# stm32.net
KiCad netlist of a schematic drawn in EAGLE
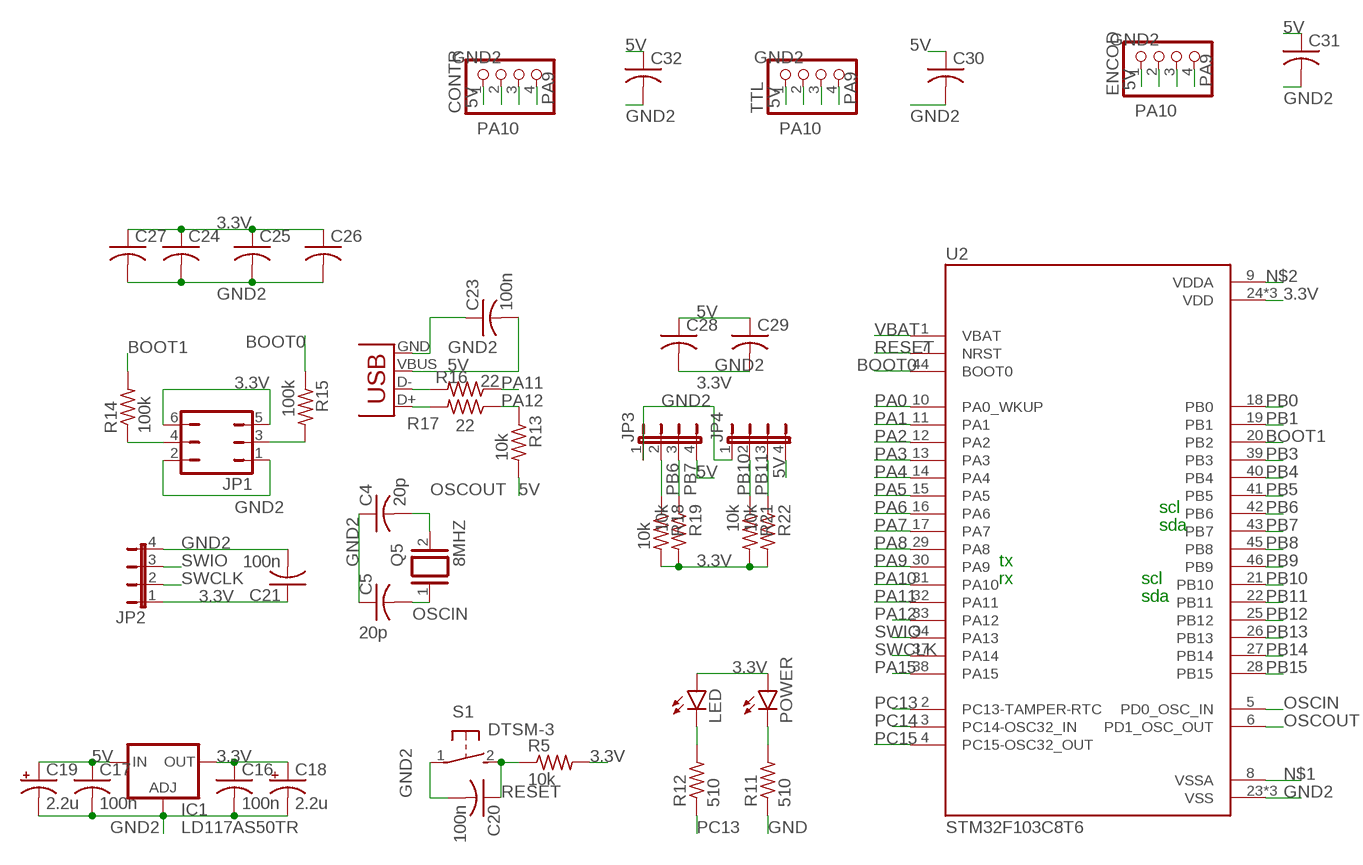
[diagram p0: schematic, sheet 1]

(export (version "E")
  (design (tool "Eeschema 10.0.6"))
  (components
    (comp (ref "C4")
      (value "20p")
      (footprint "eagle-import:C1206")
      (libsource (lib "eagle-import") (part "C-USC1206"))
    )
    (comp (ref "C5")
      (value "20p")
      (footprint "eagle-import:C1206")
      (libsource (lib "eagle-import") (part "C-USC1206"))
    )
    (comp (ref "C16")
      (value "100n")
      (footprint "eagle-import:C1206")
      (libsource (lib "eagle-import") (part "C-USC1206"))
    )
    (comp (ref "C17")
      (value "100n")
      (footprint "eagle-import:C1206")
      (libsource (lib "eagle-import") (part "C-USC1206"))
    )
    (comp (ref "C18")
      (value "2.2u")
      (footprint "eagle-import:E2-5")
      (libsource (lib "eagle-import") (part "CPOL-USE2-5"))
    )
    (comp (ref "C19")
      (value "2.2u")
      (footprint "eagle-import:E2-5")
      (libsource (lib "eagle-import") (part "CPOL-USE2-5"))
    )
    (comp (ref "C20")
      (value "100n")
      (footprint "eagle-import:C1206")
      (libsource (lib "eagle-import") (part "C-USC1206"))
    )
    (comp (ref "C21")
      (value "100n")
      (footprint "eagle-import:C1206")
      (libsource (lib "eagle-import") (part "C-USC1206"))
    )
    (comp (ref "C23")
      (value "100n")
      (footprint "eagle-import:C1206")
      (libsource (lib "eagle-import") (part "C-USC1206"))
    )
    (comp (ref "C24")
      (value "C-USC1206")
      (footprint "eagle-import:C1206")
      (libsource (lib "eagle-import") (part "C-USC1206"))
    )
    (comp (ref "C25")
      (value "C-USC1206")
      (footprint "eagle-import:C1206")
      (libsource (lib "eagle-import") (part "C-USC1206"))
    )
    (comp (ref "C26")
      (value "C-USC1206")
      (footprint "eagle-import:C1206")
      (libsource (lib "eagle-import") (part "C-USC1206"))
    )
    (comp (ref "C27")
      (value "C-USC1206")
      (footprint "eagle-import:C1206")
      (libsource (lib "eagle-import") (part "C-USC1206"))
    )
    (comp (ref "C28")
      (value "C-USC1206")
      (footprint "eagle-import:C1206")
      (libsource (lib "eagle-import") (part "C-USC1206"))
    )
    (comp (ref "C29")
      (value "C-USC1206")
      (footprint "eagle-import:C1206")
      (libsource (lib "eagle-import") (part "C-USC1206"))
    )
    (comp (ref "C30")
      (value "C-USC1206")
      (footprint "eagle-import:C1206")
      (libsource (lib "eagle-import") (part "C-USC1206"))
    )
    (comp (ref "C31")
      (value "C-USC1206")
      (footprint "eagle-import:C1206")
      (libsource (lib "eagle-import") (part "C-USC1206"))
    )
    (comp (ref "C32")
      (value "C-USC1206")
      (footprint "eagle-import:C1206")
      (libsource (lib "eagle-import") (part "C-USC1206"))
    )
    (comp (ref "CONTR")
      (value "PINHD-1X4")
      (footprint "eagle-import:1X04")
      (libsource (lib "eagle-import") (part "PINHD-1X4"))
    )
    (comp (ref "ENCOD")
      (value "PINHD-1X4")
      (footprint "eagle-import:1X04")
      (libsource (lib "eagle-import") (part "PINHD-1X4"))
    )
    (comp (ref "IC1")
      (value "LD117AS50TR")
      (footprint "eagle-import:SOT223")
      (libsource (lib "eagle-import") (part "LD117A?S50TR"))
    )
    (comp (ref "JP1")
      (value "JP3Q")
      (footprint "eagle-import:JP3Q")
      (libsource (lib "eagle-import") (part "JP3Q"))
    )
    (comp (ref "JP2")
      (value "JP4E")
      (footprint "eagle-import:JP4")
      (libsource (lib "eagle-import") (part "JP4E"))
    )
    (comp (ref "JP3")
      (value "JP4E")
      (footprint "eagle-import:JP4")
      (libsource (lib "eagle-import") (part "JP4E"))
    )
    (comp (ref "JP4")
      (value "JP4E")
      (footprint "eagle-import:JP4")
      (libsource (lib "eagle-import") (part "JP4E"))
    )
    (comp (ref "LED")
      (value "LEDCHIPLED_1206")
      (footprint "eagle-import:CHIPLED_1206")
      (libsource (lib "eagle-import") (part "LEDCHIPLED_1206"))
    )
    (comp (ref "POWER")
      (value "LEDCHIPLED_1206")
      (footprint "eagle-import:CHIPLED_1206")
      (libsource (lib "eagle-import") (part "LEDCHIPLED_1206"))
    )
    (comp (ref "Q5")
      (value "8MHZ")
      (footprint "eagle-import:QS")
      (libsource (lib "eagle-import") (part "XTAL/S"))
    )
    (comp (ref "R5")
      (value "10k")
      (footprint "eagle-import:R1206")
      (libsource (lib "eagle-import") (part "R-US_R1206"))
    )
    (comp (ref "R11")
      (value "510")
      (footprint "eagle-import:R1206")
      (libsource (lib "eagle-import") (part "R-US_R1206"))
    )
    (comp (ref "R12")
      (value "510")
      (footprint "eagle-import:R1206")
      (libsource (lib "eagle-import") (part "R-US_R1206"))
    )
    (comp (ref "R13")
      (value "10k")
      (footprint "eagle-import:R1206")
      (libsource (lib "eagle-import") (part "R-US_R1206"))
    )
    (comp (ref "R14")
      (value "100k")
      (footprint "eagle-import:R1206")
      (libsource (lib "eagle-import") (part "R-US_R1206"))
    )
    (comp (ref "R15")
      (value "100k")
      (footprint "eagle-import:R1206")
      (libsource (lib "eagle-import") (part "R-US_R1206"))
    )
    (comp (ref "R16")
      (value "22")
      (footprint "eagle-import:R1206")
      (libsource (lib "eagle-import") (part "R-US_R1206"))
    )
    (comp (ref "R17")
      (value "22")
      (footprint "eagle-import:R1206")
      (libsource (lib "eagle-import") (part "R-US_R1206"))
    )
    (comp (ref "R18")
      (value "10k")
      (footprint "eagle-import:R1206")
      (libsource (lib "eagle-import") (part "R-US_R1206"))
    )
    (comp (ref "R19")
      (value "10k")
      (footprint "eagle-import:R1206")
      (libsource (lib "eagle-import") (part "R-US_R1206"))
    )
    (comp (ref "R21")
      (value "10k")
      (footprint "eagle-import:R1206")
      (libsource (lib "eagle-import") (part "R-US_R1206"))
    )
    (comp (ref "R22")
      (value "10k")
      (footprint "eagle-import:R1206")
      (libsource (lib "eagle-import") (part "R-US_R1206"))
    )
    (comp (ref "S1")
      (value "DTSM-3")
      (footprint "eagle-import:DTSM-3")
      (libsource (lib "eagle-import") (part "DTSM-3"))
    )
    (comp (ref "TTL")
      (value "PINHD-1X4")
      (footprint "eagle-import:1X04")
      (libsource (lib "eagle-import") (part "PINHD-1X4"))
    )
    (comp (ref "U2")
      (value "STM32F103C8T6")
      (footprint "eagle-import:QFP50P900X900X160-48N")
      (fields (field (name "MF") "STMicroelectronics"))
      (libsource (lib "eagle-import") (part "STM32F103C8T6"))
    )
    (comp (ref "X1")
      (value "USB-MB-S")
      (footprint "eagle-import:USB-MB-S")
      (libsource (lib "eagle-import") (part "USB-MB-S"))
    )
  )
  (nets
    (net (code "1") (name "/3.3V") (class "Default")
      (node (ref "C16") (pin "1") (pinfunction "1_1") (pintype "passive"))
      (node (ref "C18") (pin "+") (pinfunction "+_+") (pintype "passive"))
      (node (ref "C21") (pin "1") (pinfunction "1_1") (pintype "passive"))
      (node (ref "C24") (pin "1") (pinfunction "1_1") (pintype "passive"))
      (node (ref "C25") (pin "1") (pinfunction "1_1") (pintype "passive"))
      (node (ref "C26") (pin "1") (pinfunction "1_1") (pintype "passive"))
      (node (ref "C27") (pin "1") (pinfunction "1_1") (pintype "passive"))
      (node (ref "IC1") (pin "4") (pinfunction "OUT_4") (pintype "passive"))
      (node (ref "JP1") (pin "5") (pinfunction "5_5") (pintype "passive"))
      (node (ref "JP1") (pin "6") (pinfunction "6_6") (pintype "passive"))
      (node (ref "JP2") (pin "1") (pinfunction "1_1") (pintype "passive"))
      (node (ref "LED") (pin "A") (pinfunction "A_A") (pintype "passive"))
      (node (ref "POWER") (pin "A") (pinfunction "A_A") (pintype "passive"))
      (node (ref "R18") (pin "2") (pinfunction "2_2") (pintype "passive"))
      (node (ref "R19") (pin "2") (pinfunction "2_2") (pintype "passive"))
      (node (ref "R21") (pin "2") (pinfunction "2_2") (pintype "passive"))
      (node (ref "R22") (pin "2") (pinfunction "2_2") (pintype "passive"))
      (node (ref "R5") (pin "2") (pinfunction "2_2") (pintype "passive"))
      (node (ref "U2") (pin "24") (pinfunction "VDD_24") (pintype "power_in"))
      (node (ref "U2") (pin "36") (pinfunction "VDD_36") (pintype "power_in"))
      (node (ref "U2") (pin "48") (pinfunction "VDD_48") (pintype "power_in"))
    )
    (net (code "2") (name "/5V") (class "Default")
      (node (ref "C17") (pin "1") (pinfunction "1_1") (pintype "passive"))
      (node (ref "C19") (pin "+") (pinfunction "+_+") (pintype "passive"))
      (node (ref "C23") (pin "2") (pinfunction "2_2") (pintype "passive"))
      (node (ref "C28") (pin "1") (pinfunction "1_1") (pintype "passive"))
      (node (ref "C29") (pin "1") (pinfunction "1_1") (pintype "passive"))
      (node (ref "C30") (pin "1") (pinfunction "1_1") (pintype "passive"))
      (node (ref "C31") (pin "1") (pinfunction "1_1") (pintype "passive"))
      (node (ref "C32") (pin "1") (pinfunction "1_1") (pintype "passive"))
      (node (ref "CONTR") (pin "1") (pinfunction "1_1") (pintype "passive"))
      (node (ref "ENCOD") (pin "1") (pinfunction "1_1") (pintype "passive"))
      (node (ref "IC1") (pin "3") (pinfunction "IN_3") (pintype "input"))
      (node (ref "JP3") (pin "4") (pinfunction "4_4") (pintype "passive"))
      (node (ref "JP4") (pin "4") (pinfunction "4_4") (pintype "passive"))
      (node (ref "R13") (pin "2") (pinfunction "2_2") (pintype "passive"))
      (node (ref "TTL") (pin "1") (pinfunction "1_1") (pintype "passive"))
      (node (ref "X1") (pin "VBUS") (pinfunction "VBUS_VBUS") (pintype "bidirectional"))
    )
    (net (code "3") (name "/BOOT0") (class "Default")
      (node (ref "R15") (pin "1") (pinfunction "1_1") (pintype "passive"))
      (node (ref "U2") (pin "44") (pinfunction "BOOT0_44") (pintype "input"))
    )
    (net (code "4") (name "/BOOT1") (class "Default")
      (node (ref "R14") (pin "2") (pinfunction "2_2") (pintype "passive"))
      (node (ref "U2") (pin "20") (pinfunction "PB2_20") (pintype "bidirectional"))
    )
    (net (code "5") (name "/GND") (class "Default")
      (node (ref "R11") (pin "1") (pinfunction "1_1") (pintype "passive"))
    )
    (net (code "6") (name "/GND2") (class "Default")
      (node (ref "C16") (pin "2") (pinfunction "2_2") (pintype "passive"))
      (node (ref "C17") (pin "2") (pinfunction "2_2") (pintype "passive"))
      (node (ref "C18") (pin "-") (pinfunction "-_-") (pintype "passive"))
      (node (ref "C19") (pin "-") (pinfunction "-_-") (pintype "passive"))
      (node (ref "C20") (pin "2") (pinfunction "2_2") (pintype "passive"))
      (node (ref "C21") (pin "2") (pinfunction "2_2") (pintype "passive"))
      (node (ref "C23") (pin "1") (pinfunction "1_1") (pintype "passive"))
      (node (ref "C24") (pin "2") (pinfunction "2_2") (pintype "passive"))
      (node (ref "C25") (pin "2") (pinfunction "2_2") (pintype "passive"))
      (node (ref "C26") (pin "2") (pinfunction "2_2") (pintype "passive"))
      (node (ref "C27") (pin "2") (pinfunction "2_2") (pintype "passive"))
      (node (ref "C28") (pin "2") (pinfunction "2_2") (pintype "passive"))
      (node (ref "C29") (pin "2") (pinfunction "2_2") (pintype "passive"))
      (node (ref "C30") (pin "2") (pinfunction "2_2") (pintype "passive"))
      (node (ref "C31") (pin "2") (pinfunction "2_2") (pintype "passive"))
      (node (ref "C32") (pin "2") (pinfunction "2_2") (pintype "passive"))
      (node (ref "C4") (pin "1") (pinfunction "1_1") (pintype "passive"))
      (node (ref "C5") (pin "1") (pinfunction "1_1") (pintype "passive"))
      (node (ref "CONTR") (pin "2") (pinfunction "2_2") (pintype "passive"))
      (node (ref "ENCOD") (pin "2") (pinfunction "2_2") (pintype "passive"))
      (node (ref "IC1") (pin "1") (pinfunction "ADJ_1") (pintype "input"))
      (node (ref "JP1") (pin "1") (pinfunction "1_1") (pintype "passive"))
      (node (ref "JP1") (pin "2") (pinfunction "2_2") (pintype "passive"))
      (node (ref "JP2") (pin "4") (pinfunction "4_4") (pintype "passive"))
      (node (ref "JP3") (pin "1") (pinfunction "1_1") (pintype "passive"))
      (node (ref "JP4") (pin "1") (pinfunction "1_1") (pintype "passive"))
      (node (ref "S1") (pin "1") (pinfunction "1_1") (pintype "passive"))
      (node (ref "TTL") (pin "2") (pinfunction "2_2") (pintype "passive"))
      (node (ref "U2") (pin "23") (pinfunction "VSS_23") (pintype "power_in"))
      (node (ref "U2") (pin "35") (pinfunction "VSS_35") (pintype "power_in"))
      (node (ref "U2") (pin "47") (pinfunction "VSS_47") (pintype "power_in"))
      (node (ref "X1") (pin "GND") (pinfunction "GND_GND") (pintype "bidirectional"))
    )
    (net (code "7") (name "/N$1") (class "Default")
      (node (ref "U2") (pin "8") (pinfunction "VSSA_8") (pintype "power_in"))
    )
    (net (code "8") (name "/N$2") (class "Default")
      (node (ref "U2") (pin "9") (pinfunction "VDDA_9") (pintype "power_in"))
    )
    (net (code "9") (name "/OSCIN") (class "Default")
      (node (ref "C5") (pin "2") (pinfunction "2_2") (pintype "passive"))
      (node (ref "Q5") (pin "1") (pinfunction "1_1") (pintype "passive"))
      (node (ref "U2") (pin "5") (pinfunction "PD0_OSC_IN_5") (pintype "bidirectional"))
    )
    (net (code "10") (name "/OSCOUT") (class "Default")
      (node (ref "C4") (pin "2") (pinfunction "2_2") (pintype "passive"))
      (node (ref "Q5") (pin "2") (pinfunction "2_2") (pintype "passive"))
      (node (ref "U2") (pin "6") (pinfunction "PD1_OSC_OUT_6") (pintype "bidirectional"))
    )
    (net (code "11") (name "/PA0") (class "Default")
      (node (ref "U2") (pin "10") (pinfunction "PA0_WKUP_10") (pintype "bidirectional"))
    )
    (net (code "12") (name "/PA1") (class "Default")
      (node (ref "U2") (pin "11") (pinfunction "PA1_11") (pintype "bidirectional"))
    )
    (net (code "13") (name "/PA2") (class "Default")
      (node (ref "U2") (pin "12") (pinfunction "PA2_12") (pintype "bidirectional"))
    )
    (net (code "14") (name "/PA3") (class "Default")
      (node (ref "U2") (pin "13") (pinfunction "PA3_13") (pintype "bidirectional"))
    )
    (net (code "15") (name "/PA4") (class "Default")
      (node (ref "U2") (pin "14") (pinfunction "PA4_14") (pintype "bidirectional"))
    )
    (net (code "16") (name "/PA5") (class "Default")
      (node (ref "U2") (pin "15") (pinfunction "PA5_15") (pintype "bidirectional"))
    )
    (net (code "17") (name "/PA6") (class "Default")
      (node (ref "U2") (pin "16") (pinfunction "PA6_16") (pintype "bidirectional"))
    )
    (net (code "18") (name "/PA7") (class "Default")
      (node (ref "U2") (pin "17") (pinfunction "PA7_17") (pintype "bidirectional"))
    )
    (net (code "19") (name "/PA8") (class "Default")
      (node (ref "U2") (pin "29") (pinfunction "PA8_29") (pintype "bidirectional"))
    )
    (net (code "20") (name "/PA9") (class "Default")
      (node (ref "CONTR") (pin "4") (pinfunction "4_4") (pintype "passive"))
      (node (ref "ENCOD") (pin "4") (pinfunction "4_4") (pintype "passive"))
      (node (ref "TTL") (pin "4") (pinfunction "4_4") (pintype "passive"))
      (node (ref "U2") (pin "30") (pinfunction "PA9_30") (pintype "bidirectional"))
    )
    (net (code "21") (name "/PA10") (class "Default")
      (node (ref "CONTR") (pin "3") (pinfunction "3_3") (pintype "passive"))
      (node (ref "ENCOD") (pin "3") (pinfunction "3_3") (pintype "passive"))
      (node (ref "TTL") (pin "3") (pinfunction "3_3") (pintype "passive"))
      (node (ref "U2") (pin "31") (pinfunction "PA10_31") (pintype "bidirectional"))
    )
    (net (code "22") (name "/PA11") (class "Default")
      (node (ref "R16") (pin "1") (pinfunction "1_1") (pintype "passive"))
      (node (ref "U2") (pin "32") (pinfunction "PA11_32") (pintype "bidirectional"))
    )
    (net (code "23") (name "/PA12") (class "Default")
      (node (ref "R13") (pin "1") (pinfunction "1_1") (pintype "passive"))
      (node (ref "R17") (pin "1") (pinfunction "1_1") (pintype "passive"))
      (node (ref "U2") (pin "33") (pinfunction "PA12_33") (pintype "bidirectional"))
    )
    (net (code "24") (name "/PA15") (class "Default")
      (node (ref "U2") (pin "38") (pinfunction "PA15_38") (pintype "bidirectional"))
    )
    (net (code "25") (name "/PB0") (class "Default")
      (node (ref "U2") (pin "18") (pinfunction "PB0_18") (pintype "bidirectional"))
    )
    (net (code "26") (name "/PB1") (class "Default")
      (node (ref "U2") (pin "19") (pinfunction "PB1_19") (pintype "bidirectional"))
    )
    (net (code "27") (name "/PB3") (class "Default")
      (node (ref "U2") (pin "39") (pinfunction "PB3_39") (pintype "bidirectional"))
    )
    (net (code "28") (name "/PB4") (class "Default")
      (node (ref "U2") (pin "40") (pinfunction "PB4_40") (pintype "bidirectional"))
    )
    (net (code "29") (name "/PB5") (class "Default")
      (node (ref "U2") (pin "41") (pinfunction "PB5_41") (pintype "bidirectional"))
    )
    (net (code "30") (name "/PB6") (class "Default")
      (node (ref "JP3") (pin "2") (pinfunction "2_2") (pintype "passive"))
      (node (ref "R18") (pin "1") (pinfunction "1_1") (pintype "passive"))
      (node (ref "U2") (pin "42") (pinfunction "PB6_42") (pintype "bidirectional"))
    )
    (net (code "31") (name "/PB7") (class "Default")
      (node (ref "JP3") (pin "3") (pinfunction "3_3") (pintype "passive"))
      (node (ref "R19") (pin "1") (pinfunction "1_1") (pintype "passive"))
      (node (ref "U2") (pin "43") (pinfunction "PB7_43") (pintype "bidirectional"))
    )
    (net (code "32") (name "/PB8") (class "Default")
      (node (ref "U2") (pin "45") (pinfunction "PB8_45") (pintype "bidirectional"))
    )
    (net (code "33") (name "/PB9") (class "Default")
      (node (ref "U2") (pin "46") (pinfunction "PB9_46") (pintype "bidirectional"))
    )
    (net (code "34") (name "/PB10") (class "Default")
      (node (ref "JP4") (pin "2") (pinfunction "2_2") (pintype "passive"))
      (node (ref "R21") (pin "1") (pinfunction "1_1") (pintype "passive"))
      (node (ref "U2") (pin "21") (pinfunction "PB10_21") (pintype "bidirectional"))
    )
    (net (code "35") (name "/PB11") (class "Default")
      (node (ref "JP4") (pin "3") (pinfunction "3_3") (pintype "passive"))
      (node (ref "R22") (pin "1") (pinfunction "1_1") (pintype "passive"))
      (node (ref "U2") (pin "22") (pinfunction "PB11_22") (pintype "bidirectional"))
    )
    (net (code "36") (name "/PB12") (class "Default")
      (node (ref "U2") (pin "25") (pinfunction "PB12_25") (pintype "bidirectional"))
    )
    (net (code "37") (name "/PB13") (class "Default")
      (node (ref "U2") (pin "26") (pinfunction "PB13_26") (pintype "bidirectional"))
    )
    (net (code "38") (name "/PB14") (class "Default")
      (node (ref "U2") (pin "27") (pinfunction "PB14_27") (pintype "bidirectional"))
    )
    (net (code "39") (name "/PB15") (class "Default")
      (node (ref "U2") (pin "28") (pinfunction "PB15_28") (pintype "bidirectional"))
    )
    (net (code "40") (name "/PC13") (class "Default")
      (node (ref "R12") (pin "1") (pinfunction "1_1") (pintype "passive"))
      (node (ref "U2") (pin "2") (pinfunction "PC13-TAMPER-RTC_2") (pintype "bidirectional"))
    )
    (net (code "41") (name "/PC14") (class "Default")
      (node (ref "U2") (pin "3") (pinfunction "PC14-OSC32_IN_3") (pintype "bidirectional"))
    )
    (net (code "42") (name "/PC15") (class "Default")
      (node (ref "U2") (pin "4") (pinfunction "PC15-OSC32_OUT_4") (pintype "bidirectional"))
    )
    (net (code "43") (name "/RESET") (class "Default")
      (node (ref "C20") (pin "1") (pinfunction "1_1") (pintype "passive"))
      (node (ref "R5") (pin "1") (pinfunction "1_1") (pintype "passive"))
      (node (ref "S1") (pin "2") (pinfunction "2_2") (pintype "passive"))
      (node (ref "U2") (pin "7") (pinfunction "NRST_7") (pintype "input"))
    )
    (net (code "44") (name "/SWCLK") (class "Default")
      (node (ref "JP2") (pin "2") (pinfunction "2_2") (pintype "passive"))
      (node (ref "U2") (pin "37") (pinfunction "PA14_37") (pintype "bidirectional"))
    )
    (net (code "45") (name "/SWIO") (class "Default")
      (node (ref "JP2") (pin "3") (pinfunction "3_3") (pintype "passive"))
      (node (ref "U2") (pin "34") (pinfunction "PA13_34") (pintype "bidirectional"))
    )
    (net (code "46") (name "/VBAT") (class "Default")
      (node (ref "U2") (pin "1") (pinfunction "VBAT_1") (pintype "bidirectional"))
    )
    (net (code "47") (name "Net-(JP1-Pad3)") (class "Default")
      (node (ref "JP1") (pin "3") (pinfunction "3_3") (pintype "passive"))
      (node (ref "R15") (pin "2") (pinfunction "2_2") (pintype "passive"))
    )
    (net (code "48") (name "Net-(JP1-Pad4)") (class "Default")
      (node (ref "JP1") (pin "4") (pinfunction "4_4") (pintype "passive"))
      (node (ref "R14") (pin "1") (pinfunction "1_1") (pintype "passive"))
    )
    (net (code "49") (name "Net-(LED-PadC)") (class "Default")
      (node (ref "LED") (pin "C") (pinfunction "C_C") (pintype "passive"))
      (node (ref "R12") (pin "2") (pinfunction "2_2") (pintype "passive"))
    )
    (net (code "50") (name "Net-(POWER-PadC)") (class "Default")
      (node (ref "POWER") (pin "C") (pinfunction "C_C") (pintype "passive"))
      (node (ref "R11") (pin "2") (pinfunction "2_2") (pintype "passive"))
    )
    (net (code "51") (name "Net-(R16-Pad2)") (class "Default")
      (node (ref "R16") (pin "2") (pinfunction "2_2") (pintype "passive"))
      (node (ref "X1") (pin "D-") (pinfunction "D-_D-") (pintype "bidirectional"))
    )
    (net (code "52") (name "Net-(R17-Pad2)") (class "Default")
      (node (ref "R17") (pin "2") (pinfunction "2_2") (pintype "passive"))
      (node (ref "X1") (pin "D+") (pinfunction "D+_D+") (pintype "bidirectional"))
    )
  )
)
